# StearnsMT.net
KiCad netlist of a schematic drawn in EAGLE
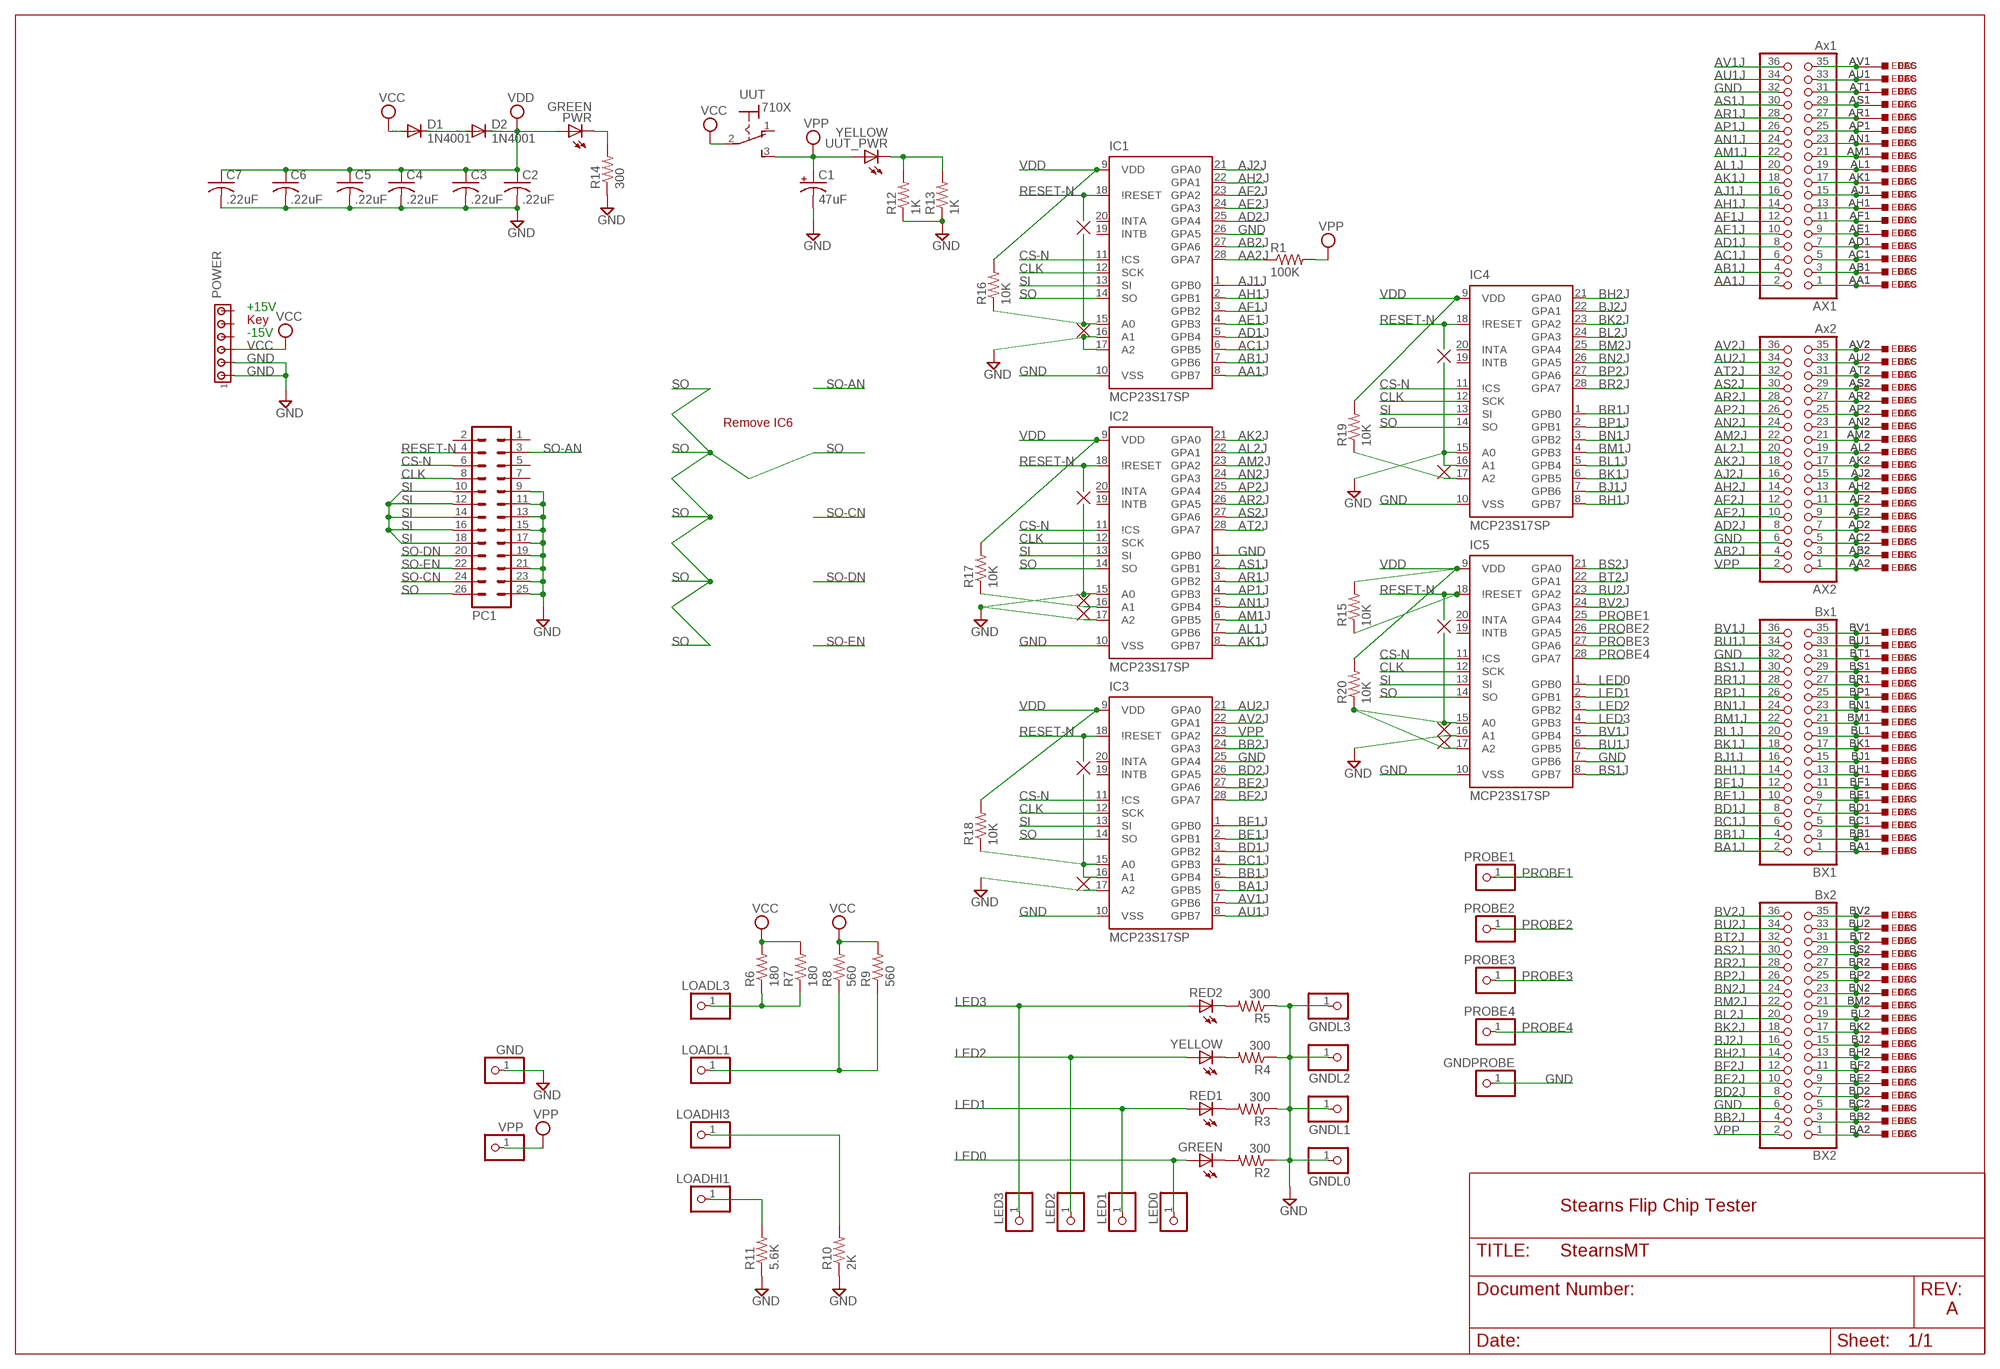
[diagram p0: schematic, sheet 1]

(export (version "E")
  (design (tool "Eeschema 10.0.6"))
  (components
    (comp (ref "AX1")
      (value "Ax1")
      (footprint "eagle-import:2X18")
      (libsource (lib "eagle-import") (part "PINHD-2X18"))
    )
    (comp (ref "AX2")
      (value "Ax2")
      (footprint "eagle-import:2X18")
      (libsource (lib "eagle-import") (part "PINHD-2X18"))
    )
    (comp (ref "BX1")
      (value "Bx1")
      (footprint "eagle-import:2X18")
      (libsource (lib "eagle-import") (part "PINHD-2X18"))
    )
    (comp (ref "BX2")
      (value "Bx2")
      (footprint "eagle-import:2X18")
      (libsource (lib "eagle-import") (part "PINHD-2X18"))
    )
    (comp (ref "C1")
      (value "47uF")
      (footprint "eagle-import:E5-8,5")
      (libsource (lib "eagle-import") (part "CPOL-USE5-8.5"))
    )
    (comp (ref "C2")
      (value ".22uF")
      (footprint "eagle-import:C050-025X075")
      (libsource (lib "eagle-import") (part "C-US050-025X075"))
    )
    (comp (ref "C3")
      (value ".22uF")
      (footprint "eagle-import:C050-025X075")
      (libsource (lib "eagle-import") (part "C-US050-025X075"))
    )
    (comp (ref "C4")
      (value ".22uF")
      (footprint "eagle-import:C050-025X075")
      (libsource (lib "eagle-import") (part "C-US050-025X075"))
    )
    (comp (ref "C5")
      (value ".22uF")
      (footprint "eagle-import:C050-025X075")
      (libsource (lib "eagle-import") (part "C-US050-025X075"))
    )
    (comp (ref "C6")
      (value ".22uF")
      (footprint "eagle-import:C050-025X075")
      (libsource (lib "eagle-import") (part "C-US050-025X075"))
    )
    (comp (ref "C7")
      (value ".22uF")
      (footprint "eagle-import:C050-025X075")
      (libsource (lib "eagle-import") (part "C-US050-025X075"))
    )
    (comp (ref "D1")
      (value "1N4001")
      (footprint "eagle-import:DO41-10")
      (libsource (lib "eagle-import") (part "1N4004"))
    )
    (comp (ref "D2")
      (value "1N4001")
      (footprint "eagle-import:DO41-10")
      (libsource (lib "eagle-import") (part "1N4004"))
    )
    (comp (ref "DEC")
      (value "W971")
      (footprint "eagle-import:H807-2")
      (libsource (lib "eagle-import") (part "W971"))
    )
    (comp (ref "ECS")
      (value "W971ECS")
      (footprint "eagle-import:ECS2418-2")
      (libsource (lib "eagle-import") (part "W971ECS"))
    )
    (comp (ref "EDAC")
      (value "W971EDAC")
      (footprint "eagle-import:EDAC346-36-2")
      (libsource (lib "eagle-import") (part "W971EDAC"))
    )
    (comp (ref "GND")
      (value "PINHD-1X1")
      (footprint "eagle-import:1X01")
      (libsource (lib "eagle-import") (part "PINHD-1X1"))
    )
    (comp (ref "GNDL0")
      (value "PINHD-1X1")
      (footprint "eagle-import:1X01")
      (libsource (lib "eagle-import") (part "PINHD-1X1"))
    )
    (comp (ref "GNDL1")
      (value "PINHD-1X1")
      (footprint "eagle-import:1X01")
      (libsource (lib "eagle-import") (part "PINHD-1X1"))
    )
    (comp (ref "GNDL2")
      (value "PINHD-1X1")
      (footprint "eagle-import:1X01")
      (libsource (lib "eagle-import") (part "PINHD-1X1"))
    )
    (comp (ref "GNDL3")
      (value "PINHD-1X1")
      (footprint "eagle-import:1X01")
      (libsource (lib "eagle-import") (part "PINHD-1X1"))
    )
    (comp (ref "GNDPROBE")
      (value "PINHD-1X1")
      (footprint "eagle-import:1X01")
      (libsource (lib "eagle-import") (part "PINHD-1X1"))
    )
    (comp (ref "GREEN")
      (value "LED5MM")
      (footprint "eagle-import:LED5MM")
      (libsource (lib "eagle-import") (part "LED5MM"))
    )
    (comp (ref "IC1")
      (value "MCP23S17SP")
      (footprint "eagle-import:DIL28-3")
      (libsource (lib "eagle-import") (part "MCP23S17SP"))
    )
    (comp (ref "IC2")
      (value "MCP23S17SP")
      (footprint "eagle-import:DIL28-3")
      (libsource (lib "eagle-import") (part "MCP23S17SP"))
    )
    (comp (ref "IC3")
      (value "MCP23S17SP")
      (footprint "eagle-import:DIL28-3")
      (libsource (lib "eagle-import") (part "MCP23S17SP"))
    )
    (comp (ref "IC4")
      (value "MCP23S17SP")
      (footprint "eagle-import:DIL28-3")
      (libsource (lib "eagle-import") (part "MCP23S17SP"))
    )
    (comp (ref "IC5")
      (value "MCP23S17SP")
      (footprint "eagle-import:DIL28-3")
      (libsource (lib "eagle-import") (part "MCP23S17SP"))
    )
    (comp (ref "LED0")
      (value "PINHD-1X1")
      (footprint "eagle-import:1X01")
      (libsource (lib "eagle-import") (part "PINHD-1X1"))
    )
    (comp (ref "LED1")
      (value "PINHD-1X1")
      (footprint "eagle-import:1X01")
      (libsource (lib "eagle-import") (part "PINHD-1X1"))
    )
    (comp (ref "LED2")
      (value "PINHD-1X1")
      (footprint "eagle-import:1X01")
      (libsource (lib "eagle-import") (part "PINHD-1X1"))
    )
    (comp (ref "LED3")
      (value "PINHD-1X1")
      (footprint "eagle-import:1X01")
      (libsource (lib "eagle-import") (part "PINHD-1X1"))
    )
    (comp (ref "LOADHI1")
      (value "PINHD-1X1")
      (footprint "eagle-import:1X01")
      (libsource (lib "eagle-import") (part "PINHD-1X1"))
    )
    (comp (ref "LOADHI3")
      (value "PINHD-1X1")
      (footprint "eagle-import:1X01")
      (libsource (lib "eagle-import") (part "PINHD-1X1"))
    )
    (comp (ref "LOADL1")
      (value "PINHD-1X1")
      (footprint "eagle-import:1X01")
      (libsource (lib "eagle-import") (part "PINHD-1X1"))
    )
    (comp (ref "LOADL3")
      (value "PINHD-1X1")
      (footprint "eagle-import:1X01")
      (libsource (lib "eagle-import") (part "PINHD-1X1"))
    )
    (comp (ref "PC1")
      (value "MA13-2")
      (footprint "eagle-import:MA13-2")
      (libsource (lib "eagle-import") (part "MA13-2"))
    )
    (comp (ref "POWER")
      (value "MTA06-156")
      (footprint "eagle-import:1X6MTA")
      (libsource (lib "eagle-import") (part "MTA06-156"))
    )
    (comp (ref "PROBE1")
      (value "PINHD-1X1")
      (footprint "eagle-import:1X01")
      (libsource (lib "eagle-import") (part "PINHD-1X1"))
    )
    (comp (ref "PROBE2")
      (value "PINHD-1X1")
      (footprint "eagle-import:1X01")
      (libsource (lib "eagle-import") (part "PINHD-1X1"))
    )
    (comp (ref "PROBE3")
      (value "PINHD-1X1")
      (footprint "eagle-import:1X01")
      (libsource (lib "eagle-import") (part "PINHD-1X1"))
    )
    (comp (ref "PROBE4")
      (value "PINHD-1X1")
      (footprint "eagle-import:1X01")
      (libsource (lib "eagle-import") (part "PINHD-1X1"))
    )
    (comp (ref "PWR")
      (value "GREEN")
      (footprint "eagle-import:LED5MM")
      (libsource (lib "eagle-import") (part "LED5MM"))
    )
    (comp (ref "R1")
      (value "100K")
      (footprint "eagle-import:0207_10")
      (libsource (lib "eagle-import") (part "R-US_0207/10"))
    )
    (comp (ref "R2")
      (value "300")
      (footprint "eagle-import:0207_10")
      (libsource (lib "eagle-import") (part "R-US_0207/10"))
    )
    (comp (ref "R3")
      (value "300")
      (footprint "eagle-import:0207_10")
      (libsource (lib "eagle-import") (part "R-US_0207/10"))
    )
    (comp (ref "R4")
      (value "300")
      (footprint "eagle-import:0207_10")
      (libsource (lib "eagle-import") (part "R-US_0207/10"))
    )
    (comp (ref "R5")
      (value "300")
      (footprint "eagle-import:0207_10")
      (libsource (lib "eagle-import") (part "R-US_0207/10"))
    )
    (comp (ref "R6")
      (value "180")
      (footprint "eagle-import:0207_10")
      (libsource (lib "eagle-import") (part "R-US_0207/10"))
    )
    (comp (ref "R7")
      (value "180")
      (footprint "eagle-import:0207_10")
      (libsource (lib "eagle-import") (part "R-US_0207/10"))
    )
    (comp (ref "R8")
      (value "560")
      (footprint "eagle-import:0207_10")
      (libsource (lib "eagle-import") (part "R-US_0207/10"))
    )
    (comp (ref "R9")
      (value "560")
      (footprint "eagle-import:0207_10")
      (libsource (lib "eagle-import") (part "R-US_0207/10"))
    )
    (comp (ref "R10")
      (value "2K")
      (footprint "eagle-import:0207_10")
      (libsource (lib "eagle-import") (part "R-US_0207/10"))
    )
    (comp (ref "R11")
      (value "5.6K")
      (footprint "eagle-import:0207_10")
      (libsource (lib "eagle-import") (part "R-US_0207/10"))
    )
    (comp (ref "R12")
      (value "1K")
      (footprint "eagle-import:0207_10")
      (libsource (lib "eagle-import") (part "R-US_0207/10"))
    )
    (comp (ref "R13")
      (value "1K")
      (footprint "eagle-import:0207_10")
      (libsource (lib "eagle-import") (part "R-US_0207/10"))
    )
    (comp (ref "R14")
      (value "300")
      (footprint "eagle-import:0207_10")
      (libsource (lib "eagle-import") (part "R-US_0207/10"))
    )
    (comp (ref "R15")
      (value "10K")
      (footprint "eagle-import:0207_10")
      (libsource (lib "eagle-import") (part "R-US_0207/10"))
    )
    (comp (ref "R16")
      (value "10K")
      (footprint "eagle-import:0207_10")
      (libsource (lib "eagle-import") (part "R-US_0207/10"))
    )
    (comp (ref "R17")
      (value "10K")
      (footprint "eagle-import:0207_10")
      (libsource (lib "eagle-import") (part "R-US_0207/10"))
    )
    (comp (ref "R18")
      (value "10K")
      (footprint "eagle-import:0207_10")
      (libsource (lib "eagle-import") (part "R-US_0207/10"))
    )
    (comp (ref "R19")
      (value "10K")
      (footprint "eagle-import:0207_10")
      (libsource (lib "eagle-import") (part "R-US_0207/10"))
    )
    (comp (ref "R20")
      (value "10K")
      (footprint "eagle-import:0207_10")
      (libsource (lib "eagle-import") (part "R-US_0207/10"))
    )
    (comp (ref "RED1")
      (value "LED5MM")
      (footprint "eagle-import:LED5MM")
      (libsource (lib "eagle-import") (part "LED5MM"))
    )
    (comp (ref "RED2")
      (value "LED5MM")
      (footprint "eagle-import:LED5MM")
      (libsource (lib "eagle-import") (part "LED5MM"))
    )
    (comp (ref "UUT")
      (value "710X")
      (footprint "eagle-import:7109MD9V3")
      (libsource (lib "eagle-import") (part "710X"))
    )
    (comp (ref "UUT_PWR")
      (value "YELLOW")
      (footprint "eagle-import:LED5MM")
      (libsource (lib "eagle-import") (part "LED5MM"))
    )
    (comp (ref "VPP")
      (value "PINHD-1X1")
      (footprint "eagle-import:1X01")
      (libsource (lib "eagle-import") (part "PINHD-1X1"))
    )
    (comp (ref "YELLOW")
      (value "LED5MM")
      (footprint "eagle-import:LED5MM")
      (libsource (lib "eagle-import") (part "LED5MM"))
    )
  )
  (nets
    (net (code "1") (name "/AA1J") (class "Default")
      (node (ref "AX1") (pin "2") (pinfunction "2_2") (pintype "passive"))
      (node (ref "IC1") (pin "8") (pinfunction "GPB7_8") (pintype "bidirectional"))
    )
    (net (code "2") (name "/AA2J") (class "Default")
      (node (ref "IC1") (pin "28") (pinfunction "GPA7_28") (pintype "bidirectional"))
      (node (ref "R1") (pin "1") (pinfunction "1_1") (pintype "passive"))
    )
    (net (code "3") (name "/AB1J") (class "Default")
      (node (ref "AX1") (pin "4") (pinfunction "4_4") (pintype "passive"))
      (node (ref "IC1") (pin "7") (pinfunction "GPB6_7") (pintype "bidirectional"))
    )
    (net (code "4") (name "/AB2J") (class "Default")
      (node (ref "AX2") (pin "4") (pinfunction "4_4") (pintype "passive"))
      (node (ref "IC1") (pin "27") (pinfunction "GPA6_27") (pintype "bidirectional"))
    )
    (net (code "5") (name "/AC1J") (class "Default")
      (node (ref "AX1") (pin "6") (pinfunction "6_6") (pintype "passive"))
      (node (ref "IC1") (pin "6") (pinfunction "GPB5_6") (pintype "bidirectional"))
    )
    (net (code "6") (name "/AD1J") (class "Default")
      (node (ref "AX1") (pin "8") (pinfunction "8_8") (pintype "passive"))
      (node (ref "IC1") (pin "5") (pinfunction "GPB4_5") (pintype "bidirectional"))
    )
    (net (code "7") (name "/AD2J") (class "Default")
      (node (ref "AX2") (pin "8") (pinfunction "8_8") (pintype "passive"))
      (node (ref "IC1") (pin "25") (pinfunction "GPA4_25") (pintype "bidirectional"))
    )
    (net (code "8") (name "/AE1J") (class "Default")
      (node (ref "AX1") (pin "10") (pinfunction "10_10") (pintype "passive"))
      (node (ref "IC1") (pin "4") (pinfunction "GPB3_4") (pintype "bidirectional"))
    )
    (net (code "9") (name "/AE2J") (class "Default")
      (node (ref "AX2") (pin "10") (pinfunction "10_10") (pintype "passive"))
      (node (ref "IC1") (pin "24") (pinfunction "GPA3_24") (pintype "bidirectional"))
    )
    (net (code "10") (name "/AF1J") (class "Default")
      (node (ref "AX1") (pin "12") (pinfunction "12_12") (pintype "passive"))
      (node (ref "IC1") (pin "3") (pinfunction "GPB2_3") (pintype "bidirectional"))
    )
    (net (code "11") (name "/AF2J") (class "Default")
      (node (ref "AX2") (pin "12") (pinfunction "12_12") (pintype "passive"))
      (node (ref "IC1") (pin "23") (pinfunction "GPA2_23") (pintype "bidirectional"))
    )
    (net (code "12") (name "/AH1J") (class "Default")
      (node (ref "AX1") (pin "14") (pinfunction "14_14") (pintype "passive"))
      (node (ref "IC1") (pin "2") (pinfunction "GPB1_2") (pintype "bidirectional"))
    )
    (net (code "13") (name "/AH2J") (class "Default")
      (node (ref "AX2") (pin "14") (pinfunction "14_14") (pintype "passive"))
      (node (ref "IC1") (pin "22") (pinfunction "GPA1_22") (pintype "bidirectional"))
    )
    (net (code "14") (name "/AJ1J") (class "Default")
      (node (ref "AX1") (pin "16") (pinfunction "16_16") (pintype "passive"))
      (node (ref "IC1") (pin "1") (pinfunction "GPB0_1") (pintype "bidirectional"))
    )
    (net (code "15") (name "/AJ2J") (class "Default")
      (node (ref "AX2") (pin "16") (pinfunction "16_16") (pintype "passive"))
      (node (ref "IC1") (pin "21") (pinfunction "GPA0_21") (pintype "bidirectional"))
    )
    (net (code "16") (name "/AK1J") (class "Default")
      (node (ref "AX1") (pin "18") (pinfunction "18_18") (pintype "passive"))
      (node (ref "IC2") (pin "8") (pinfunction "GPB7_8") (pintype "bidirectional"))
    )
    (net (code "17") (name "/AK2J") (class "Default")
      (node (ref "AX2") (pin "18") (pinfunction "18_18") (pintype "passive"))
      (node (ref "IC2") (pin "21") (pinfunction "GPA0_21") (pintype "bidirectional"))
    )
    (net (code "18") (name "/AL1J") (class "Default")
      (node (ref "AX1") (pin "20") (pinfunction "20_20") (pintype "passive"))
      (node (ref "IC2") (pin "7") (pinfunction "GPB6_7") (pintype "bidirectional"))
    )
    (net (code "19") (name "/AL2J") (class "Default")
      (node (ref "AX2") (pin "20") (pinfunction "20_20") (pintype "passive"))
      (node (ref "IC2") (pin "22") (pinfunction "GPA1_22") (pintype "bidirectional"))
    )
    (net (code "20") (name "/AM1J") (class "Default")
      (node (ref "AX1") (pin "22") (pinfunction "22_22") (pintype "passive"))
      (node (ref "IC2") (pin "6") (pinfunction "GPB5_6") (pintype "bidirectional"))
    )
    (net (code "21") (name "/AM2J") (class "Default")
      (node (ref "AX2") (pin "22") (pinfunction "22_22") (pintype "passive"))
      (node (ref "IC2") (pin "23") (pinfunction "GPA2_23") (pintype "bidirectional"))
    )
    (net (code "22") (name "/AN1J") (class "Default")
      (node (ref "AX1") (pin "24") (pinfunction "24_24") (pintype "passive"))
      (node (ref "IC2") (pin "5") (pinfunction "GPB4_5") (pintype "bidirectional"))
    )
    (net (code "23") (name "/AN2J") (class "Default")
      (node (ref "AX2") (pin "24") (pinfunction "24_24") (pintype "passive"))
      (node (ref "IC2") (pin "24") (pinfunction "GPA3_24") (pintype "bidirectional"))
    )
    (net (code "24") (name "/AP1J") (class "Default")
      (node (ref "AX1") (pin "26") (pinfunction "26_26") (pintype "passive"))
      (node (ref "IC2") (pin "4") (pinfunction "GPB3_4") (pintype "bidirectional"))
    )
    (net (code "25") (name "/AP2J") (class "Default")
      (node (ref "AX2") (pin "26") (pinfunction "26_26") (pintype "passive"))
      (node (ref "IC2") (pin "25") (pinfunction "GPA4_25") (pintype "bidirectional"))
    )
    (net (code "26") (name "/AR1J") (class "Default")
      (node (ref "AX1") (pin "28") (pinfunction "28_28") (pintype "passive"))
      (node (ref "IC2") (pin "3") (pinfunction "GPB2_3") (pintype "bidirectional"))
    )
    (net (code "27") (name "/AR2J") (class "Default")
      (node (ref "AX2") (pin "28") (pinfunction "28_28") (pintype "passive"))
      (node (ref "IC2") (pin "26") (pinfunction "GPA5_26") (pintype "bidirectional"))
    )
    (net (code "28") (name "/AS1J") (class "Default")
      (node (ref "AX1") (pin "30") (pinfunction "30_30") (pintype "passive"))
      (node (ref "IC2") (pin "2") (pinfunction "GPB1_2") (pintype "bidirectional"))
    )
    (net (code "29") (name "/AS2J") (class "Default")
      (node (ref "AX2") (pin "30") (pinfunction "30_30") (pintype "passive"))
      (node (ref "IC2") (pin "27") (pinfunction "GPA6_27") (pintype "bidirectional"))
    )
    (net (code "30") (name "/AT2J") (class "Default")
      (node (ref "AX2") (pin "32") (pinfunction "32_32") (pintype "passive"))
      (node (ref "IC2") (pin "28") (pinfunction "GPA7_28") (pintype "bidirectional"))
    )
    (net (code "31") (name "/AU1J") (class "Default")
      (node (ref "AX1") (pin "34") (pinfunction "34_34") (pintype "passive"))
      (node (ref "IC3") (pin "8") (pinfunction "GPB7_8") (pintype "bidirectional"))
    )
    (net (code "32") (name "/AU2J") (class "Default")
      (node (ref "AX2") (pin "34") (pinfunction "34_34") (pintype "passive"))
      (node (ref "IC3") (pin "21") (pinfunction "GPA0_21") (pintype "bidirectional"))
    )
    (net (code "33") (name "/AV1J") (class "Default")
      (node (ref "AX1") (pin "36") (pinfunction "36_36") (pintype "passive"))
      (node (ref "IC3") (pin "7") (pinfunction "GPB6_7") (pintype "bidirectional"))
    )
    (net (code "34") (name "/AV2J") (class "Default")
      (node (ref "AX2") (pin "36") (pinfunction "36_36") (pintype "passive"))
      (node (ref "IC3") (pin "22") (pinfunction "GPA1_22") (pintype "bidirectional"))
    )
    (net (code "35") (name "/BA1J") (class "Default")
      (node (ref "BX1") (pin "2") (pinfunction "2_2") (pintype "passive"))
      (node (ref "IC3") (pin "6") (pinfunction "GPB5_6") (pintype "bidirectional"))
    )
    (net (code "36") (name "/BB1J") (class "Default")
      (node (ref "BX1") (pin "4") (pinfunction "4_4") (pintype "passive"))
      (node (ref "IC3") (pin "5") (pinfunction "GPB4_5") (pintype "bidirectional"))
    )
    (net (code "37") (name "/BB2J") (class "Default")
      (node (ref "BX2") (pin "4") (pinfunction "4_4") (pintype "passive"))
      (node (ref "IC3") (pin "24") (pinfunction "GPA3_24") (pintype "bidirectional"))
    )
    (net (code "38") (name "/BC1J") (class "Default")
      (node (ref "BX1") (pin "6") (pinfunction "6_6") (pintype "passive"))
      (node (ref "IC3") (pin "4") (pinfunction "GPB3_4") (pintype "bidirectional"))
    )
    (net (code "39") (name "/BD1J") (class "Default")
      (node (ref "BX1") (pin "8") (pinfunction "8_8") (pintype "passive"))
      (node (ref "IC3") (pin "3") (pinfunction "GPB2_3") (pintype "bidirectional"))
    )
    (net (code "40") (name "/BD2J") (class "Default")
      (node (ref "BX2") (pin "8") (pinfunction "8_8") (pintype "passive"))
      (node (ref "IC3") (pin "26") (pinfunction "GPA5_26") (pintype "bidirectional"))
    )
    (net (code "41") (name "/BE1J") (class "Default")
      (node (ref "BX1") (pin "10") (pinfunction "10_10") (pintype "passive"))
      (node (ref "IC3") (pin "2") (pinfunction "GPB1_2") (pintype "bidirectional"))
    )
    (net (code "42") (name "/BE2J") (class "Default")
      (node (ref "BX2") (pin "10") (pinfunction "10_10") (pintype "passive"))
      (node (ref "IC3") (pin "27") (pinfunction "GPA6_27") (pintype "bidirectional"))
    )
    (net (code "43") (name "/BF1J") (class "Default")
      (node (ref "BX1") (pin "12") (pinfunction "12_12") (pintype "passive"))
      (node (ref "IC3") (pin "1") (pinfunction "GPB0_1") (pintype "bidirectional"))
    )
    (net (code "44") (name "/BF2J") (class "Default")
      (node (ref "BX2") (pin "12") (pinfunction "12_12") (pintype "passive"))
      (node (ref "IC3") (pin "28") (pinfunction "GPA7_28") (pintype "bidirectional"))
    )
    (net (code "45") (name "/BH1J") (class "Default")
      (node (ref "BX1") (pin "14") (pinfunction "14_14") (pintype "passive"))
      (node (ref "IC4") (pin "8") (pinfunction "GPB7_8") (pintype "bidirectional"))
    )
    (net (code "46") (name "/BH2J") (class "Default")
      (node (ref "BX2") (pin "14") (pinfunction "14_14") (pintype "passive"))
      (node (ref "IC4") (pin "21") (pinfunction "GPA0_21") (pintype "bidirectional"))
    )
    (net (code "47") (name "/BJ1J") (class "Default")
      (node (ref "BX1") (pin "16") (pinfunction "16_16") (pintype "passive"))
      (node (ref "IC4") (pin "7") (pinfunction "GPB6_7") (pintype "bidirectional"))
    )
    (net (code "48") (name "/BJ2J") (class "Default")
      (node (ref "BX2") (pin "16") (pinfunction "16_16") (pintype "passive"))
      (node (ref "IC4") (pin "22") (pinfunction "GPA1_22") (pintype "bidirectional"))
    )
    (net (code "49") (name "/BK1J") (class "Default")
      (node (ref "BX1") (pin "18") (pinfunction "18_18") (pintype "passive"))
      (node (ref "IC4") (pin "6") (pinfunction "GPB5_6") (pintype "bidirectional"))
    )
    (net (code "50") (name "/BK2J") (class "Default")
      (node (ref "BX2") (pin "18") (pinfunction "18_18") (pintype "passive"))
      (node (ref "IC4") (pin "23") (pinfunction "GPA2_23") (pintype "bidirectional"))
    )
    (net (code "51") (name "/BL1J") (class "Default")
      (node (ref "BX1") (pin "20") (pinfunction "20_20") (pintype "passive"))
      (node (ref "IC4") (pin "5") (pinfunction "GPB4_5") (pintype "bidirectional"))
    )
    (net (code "52") (name "/BL2J") (class "Default")
      (node (ref "BX2") (pin "20") (pinfunction "20_20") (pintype "passive"))
      (node (ref "IC4") (pin "24") (pinfunction "GPA3_24") (pintype "bidirectional"))
    )
    (net (code "53") (name "/BM1J") (class "Default")
      (node (ref "BX1") (pin "22") (pinfunction "22_22") (pintype "passive"))
      (node (ref "IC4") (pin "4") (pinfunction "GPB3_4") (pintype "bidirectional"))
    )
    (net (code "54") (name "/BM2J") (class "Default")
      (node (ref "BX2") (pin "22") (pinfunction "22_22") (pintype "passive"))
      (node (ref "IC4") (pin "25") (pinfunction "GPA4_25") (pintype "bidirectional"))
    )
    (net (code "55") (name "/BN1J") (class "Default")
      (node (ref "BX1") (pin "24") (pinfunction "24_24") (pintype "passive"))
      (node (ref "IC4") (pin "3") (pinfunction "GPB2_3") (pintype "bidirectional"))
    )
    (net (code "56") (name "/BN2J") (class "Default")
      (node (ref "BX2") (pin "24") (pinfunction "24_24") (pintype "passive"))
      (node (ref "IC4") (pin "26") (pinfunction "GPA5_26") (pintype "bidirectional"))
    )
    (net (code "57") (name "/BP1J") (class "Default")
      (node (ref "BX1") (pin "26") (pinfunction "26_26") (pintype "passive"))
      (node (ref "IC4") (pin "2") (pinfunction "GPB1_2") (pintype "bidirectional"))
    )
    (net (code "58") (name "/BP2J") (class "Default")
      (node (ref "BX2") (pin "26") (pinfunction "26_26") (pintype "passive"))
      (node (ref "IC4") (pin "27") (pinfunction "GPA6_27") (pintype "bidirectional"))
    )
    (net (code "59") (name "/BR1J") (class "Default")
      (node (ref "BX1") (pin "28") (pinfunction "28_28") (pintype "passive"))
      (node (ref "IC4") (pin "1") (pinfunction "GPB0_1") (pintype "bidirectional"))
    )
    (net (code "60") (name "/BR2J") (class "Default")
      (node (ref "BX2") (pin "28") (pinfunction "28_28") (pintype "passive"))
      (node (ref "IC4") (pin "28") (pinfunction "GPA7_28") (pintype "bidirectional"))
    )
    (net (code "61") (name "/BS1J") (class "Default")
      (node (ref "BX1") (pin "30") (pinfunction "30_30") (pintype "passive"))
      (node (ref "IC5") (pin "8") (pinfunction "GPB7_8") (pintype "bidirectional"))
    )
    (net (code "62") (name "/BS2J") (class "Default")
      (node (ref "BX2") (pin "30") (pinfunction "30_30") (pintype "passive"))
      (node (ref "IC5") (pin "21") (pinfunction "GPA0_21") (pintype "bidirectional"))
    )
    (net (code "63") (name "/BT2J") (class "Default")
      (node (ref "BX2") (pin "32") (pinfunction "32_32") (pintype "passive"))
      (node (ref "IC5") (pin "22") (pinfunction "GPA1_22") (pintype "bidirectional"))
    )
    (net (code "64") (name "/BU1J") (class "Default")
      (node (ref "BX1") (pin "34") (pinfunction "34_34") (pintype "passive"))
      (node (ref "IC5") (pin "6") (pinfunction "GPB5_6") (pintype "bidirectional"))
    )
    (net (code "65") (name "/BU2J") (class "Default")
      (node (ref "BX2") (pin "34") (pinfunction "34_34") (pintype "passive"))
      (node (ref "IC5") (pin "23") (pinfunction "GPA2_23") (pintype "bidirectional"))
    )
    (net (code "66") (name "/BV1J") (class "Default")
      (node (ref "BX1") (pin "36") (pinfunction "36_36") (pintype "passive"))
      (node (ref "IC5") (pin "5") (pinfunction "GPB4_5") (pintype "bidirectional"))
    )
    (net (code "67") (name "/BV2J") (class "Default")
      (node (ref "BX2") (pin "36") (pinfunction "36_36") (pintype "passive"))
      (node (ref "IC5") (pin "24") (pinfunction "GPA3_24") (pintype "bidirectional"))
    )
    (net (code "68") (name "/CLK") (class "Default")
      (node (ref "IC1") (pin "12") (pinfunction "SCK_12") (pintype "input"))
      (node (ref "IC2") (pin "12") (pinfunction "SCK_12") (pintype "input"))
      (node (ref "IC3") (pin "12") (pinfunction "SCK_12") (pintype "input"))
      (node (ref "IC4") (pin "12") (pinfunction "SCK_12") (pintype "input"))
      (node (ref "IC5") (pin "12") (pinfunction "SCK_12") (pintype "input"))
      (node (ref "PC1") (pin "8") (pinfunction "8_8") (pintype "passive"))
    )
    (net (code "69") (name "/CS-N") (class "Default")
      (node (ref "IC1") (pin "11") (pinfunction "\\~{CS}_11") (pintype "input"))
      (node (ref "IC2") (pin "11") (pinfunction "\\~{CS}_11") (pintype "input"))
      (node (ref "IC3") (pin "11") (pinfunction "\\~{CS}_11") (pintype "input"))
      (node (ref "IC4") (pin "11") (pinfunction "\\~{CS}_11") (pintype "input"))
      (node (ref "IC5") (pin "11") (pinfunction "\\~{CS}_11") (pintype "input"))
      (node (ref "PC1") (pin "6") (pinfunction "6_6") (pintype "passive"))
    )
    (net (code "70") (name "/LED0") (class "Default")
      (node (ref "GREEN") (pin "A") (pinfunction "A_A") (pintype "passive"))
      (node (ref "IC5") (pin "1") (pinfunction "GPB0_1") (pintype "bidirectional"))
      (node (ref "LED0") (pin "1") (pinfunction "1_1") (pintype "passive"))
    )
    (net (code "71") (name "/LED1") (class "Default")
      (node (ref "IC5") (pin "2") (pinfunction "GPB1_2") (pintype "bidirectional"))
      (node (ref "LED1") (pin "1") (pinfunction "1_1") (pintype "passive"))
      (node (ref "RED1") (pin "A") (pinfunction "A_A") (pintype "passive"))
    )
    (net (code "72") (name "/LED2") (class "Default")
      (node (ref "IC5") (pin "3") (pinfunction "GPB2_3") (pintype "bidirectional"))
      (node (ref "LED2") (pin "1") (pinfunction "1_1") (pintype "passive"))
      (node (ref "YELLOW") (pin "A") (pinfunction "A_A") (pintype "passive"))
    )
    (net (code "73") (name "/LED3") (class "Default")
      (node (ref "IC5") (pin "4") (pinfunction "GPB3_4") (pintype "bidirectional"))
      (node (ref "LED3") (pin "1") (pinfunction "1_1") (pintype "passive"))
      (node (ref "RED2") (pin "A") (pinfunction "A_A") (pintype "passive"))
    )
    (net (code "74") (name "/PROBE1") (class "Default")
      (node (ref "IC5") (pin "25") (pinfunction "GPA4_25") (pintype "bidirectional"))
      (node (ref "PROBE1") (pin "1") (pinfunction "1_1") (pintype "passive"))
    )
    (net (code "75") (name "/PROBE2") (class "Default")
      (node (ref "IC5") (pin "26") (pinfunction "GPA5_26") (pintype "bidirectional"))
      (node (ref "PROBE2") (pin "1") (pinfunction "1_1") (pintype "passive"))
    )
    (net (code "76") (name "/PROBE3") (class "Default")
      (node (ref "IC5") (pin "27") (pinfunction "GPA6_27") (pintype "bidirectional"))
      (node (ref "PROBE3") (pin "1") (pinfunction "1_1") (pintype "passive"))
    )
    (net (code "77") (name "/PROBE4") (class "Default")
      (node (ref "IC5") (pin "28") (pinfunction "GPA7_28") (pintype "bidirectional"))
      (node (ref "PROBE4") (pin "1") (pinfunction "1_1") (pintype "passive"))
    )
    (net (code "78") (name "/RESET-N") (class "Default")
      (node (ref "IC1") (pin "18") (pinfunction "\\~{RESET}_18") (pintype "input"))
      (node (ref "IC2") (pin "18") (pinfunction "\\~{RESET}_18") (pintype "input"))
      (node (ref "IC3") (pin "18") (pinfunction "\\~{RESET}_18") (pintype "input"))
      (node (ref "IC4") (pin "18") (pinfunction "\\~{RESET}_18") (pintype "input"))
      (node (ref "IC5") (pin "18") (pinfunction "\\~{RESET}_18") (pintype "input"))
      (node (ref "PC1") (pin "4") (pinfunction "4_4") (pintype "passive"))
      (node (ref "R15") (pin "1") (pinfunction "1_1") (pintype "passive"))
    )
    (net (code "79") (name "/SI") (class "Default")
      (node (ref "IC1") (pin "13") (pinfunction "SI_13") (pintype "input"))
      (node (ref "IC2") (pin "13") (pinfunction "SI_13") (pintype "input"))
      (node (ref "IC3") (pin "13") (pinfunction "SI_13") (pintype "input"))
      (node (ref "IC4") (pin "13") (pinfunction "SI_13") (pintype "input"))
      (node (ref "IC5") (pin "13") (pinfunction "SI_13") (pintype "input"))
      (node (ref "PC1") (pin "10") (pinfunction "10_10") (pintype "passive"))
      (node (ref "PC1") (pin "12") (pinfunction "12_12") (pintype "passive"))
      (node (ref "PC1") (pin "14") (pinfunction "14_14") (pintype "passive"))
      (node (ref "PC1") (pin "16") (pinfunction "16_16") (pintype "passive"))
      (node (ref "PC1") (pin "18") (pinfunction "18_18") (pintype "passive"))
    )
    (net (code "80") (name "/SO") (class "Default")
      (node (ref "IC1") (pin "14") (pinfunction "SO_14") (pintype "output"))
      (node (ref "IC2") (pin "14") (pinfunction "SO_14") (pintype "output"))
      (node (ref "IC3") (pin "14") (pinfunction "SO_14") (pintype "output"))
      (node (ref "IC4") (pin "14") (pinfunction "SO_14") (pintype "output"))
      (node (ref "IC5") (pin "14") (pinfunction "SO_14") (pintype "output"))
      (node (ref "PC1") (pin "26") (pinfunction "26_26") (pintype "passive"))
    )
    (net (code "81") (name "/SO-AN") (class "Default")
      (node (ref "PC1") (pin "3") (pinfunction "3_3") (pintype "passive"))
    )
    (net (code "82") (name "/SO-CN") (class "Default")
      (node (ref "PC1") (pin "24") (pinfunction "24_24") (pintype "passive"))
    )
    (net (code "83") (name "/SO-DN") (class "Default")
      (node (ref "PC1") (pin "20") (pinfunction "20_20") (pintype "passive"))
    )
    (net (code "84") (name "/SO-EN") (class "Default")
      (node (ref "PC1") (pin "22") (pinfunction "22_22") (pintype "passive"))
    )
    (net (code "85") (name "GND") (class "Default")
      (node (ref "AX1") (pin "32") (pinfunction "32_32") (pintype "passive"))
      (node (ref "AX2") (pin "6") (pinfunction "6_6") (pintype "passive"))
      (node (ref "BX1") (pin "32") (pinfunction "32_32") (pintype "passive"))
      (node (ref "BX2") (pin "6") (pinfunction "6_6") (pintype "passive"))
      (node (ref "C1") (pin "-") (pinfunction "-_-") (pintype "passive"))
      (node (ref "C2") (pin "2") (pinfunction "2_2") (pintype "passive"))
      (node (ref "C3") (pin "2") (pinfunction "2_2") (pintype "passive"))
      (node (ref "C4") (pin "2") (pinfunction "2_2") (pintype "passive"))
      (node (ref "C5") (pin "2") (pinfunction "2_2") (pintype "passive"))
      (node (ref "C6") (pin "2") (pinfunction "2_2") (pintype "passive"))
      (node (ref "C7") (pin "2") (pinfunction "2_2") (pintype "passive"))
      (node (ref "GND") (pin "1") (pinfunction "1_1") (pintype "passive"))
      (node (ref "GNDL0") (pin "1") (pinfunction "1_1") (pintype "passive"))
      (node (ref "GNDL1") (pin "1") (pinfunction "1_1") (pintype "passive"))
      (node (ref "GNDL2") (pin "1") (pinfunction "1_1") (pintype "passive"))
      (node (ref "GNDL3") (pin "1") (pinfunction "1_1") (pintype "passive"))
      (node (ref "GNDPROBE") (pin "1") (pinfunction "1_1") (pintype "passive"))
      (node (ref "IC1") (pin "10") (pinfunction "VSS_10") (pintype "power_in"))
      (node (ref "IC1") (pin "16") (pinfunction "A1_16") (pintype "input"))
      (node (ref "IC1") (pin "17") (pinfunction "A2_17") (pintype "input"))
      (node (ref "IC1") (pin "26") (pinfunction "GPA5_26") (pintype "bidirectional"))
      (node (ref "IC2") (pin "1") (pinfunction "GPB0_1") (pintype "bidirectional"))
      (node (ref "IC2") (pin "10") (pinfunction "VSS_10") (pintype "power_in"))
      (node (ref "IC2") (pin "15") (pinfunction "A0_15") (pintype "input"))
      (node (ref "IC2") (pin "17") (pinfunction "A2_17") (pintype "input"))
      (node (ref "IC3") (pin "10") (pinfunction "VSS_10") (pintype "power_in"))
      (node (ref "IC3") (pin "17") (pinfunction "A2_17") (pintype "input"))
      (node (ref "IC3") (pin "25") (pinfunction "GPA4_25") (pintype "bidirectional"))
      (node (ref "IC4") (pin "10") (pinfunction "VSS_10") (pintype "power_in"))
      (node (ref "IC4") (pin "15") (pinfunction "A0_15") (pintype "input"))
      (node (ref "IC4") (pin "16") (pinfunction "A1_16") (pintype "input"))
      (node (ref "IC5") (pin "10") (pinfunction "VSS_10") (pintype "power_in"))
      (node (ref "IC5") (pin "16") (pinfunction "A1_16") (pintype "input"))
      (node (ref "IC5") (pin "7") (pinfunction "GPB6_7") (pintype "bidirectional"))
      (node (ref "PC1") (pin "11") (pinfunction "11_11") (pintype "passive"))
      (node (ref "PC1") (pin "13") (pinfunction "13_13") (pintype "passive"))
      (node (ref "PC1") (pin "15") (pinfunction "15_15") (pintype "passive"))
      (node (ref "PC1") (pin "17") (pinfunction "17_17") (pintype "passive"))
      (node (ref "PC1") (pin "19") (pinfunction "19_19") (pintype "passive"))
      (node (ref "PC1") (pin "21") (pinfunction "21_21") (pintype "passive"))
      (node (ref "PC1") (pin "23") (pinfunction "23_23") (pintype "passive"))
      (node (ref "PC1") (pin "25") (pinfunction "25_25") (pintype "passive"))
      (node (ref "PC1") (pin "9") (pinfunction "9_9") (pintype "passive"))
      (node (ref "POWER") (pin "1") (pinfunction "1_1") (pintype "passive"))
      (node (ref "POWER") (pin "2") (pinfunction "2_2") (pintype "passive"))
      (node (ref "R10") (pin "1") (pinfunction "1_1") (pintype "passive"))
      (node (ref "R11") (pin "1") (pinfunction "1_1") (pintype "passive"))
      (node (ref "R12") (pin "1") (pinfunction "1_1") (pintype "passive"))
      (node (ref "R13") (pin "1") (pinfunction "1_1") (pintype "passive"))
      (node (ref "R14") (pin "1") (pinfunction "1_1") (pintype "passive"))
      (node (ref "R2") (pin "1") (pinfunction "1_1") (pintype "passive"))
      (node (ref "R3") (pin "1") (pinfunction "1_1") (pintype "passive"))
      (node (ref "R4") (pin "1") (pinfunction "1_1") (pintype "passive"))
      (node (ref "R5") (pin "1") (pinfunction "1_1") (pintype "passive"))
    )
    (net (code "86") (name "Net-(D1-PadC)") (class "Default")
      (node (ref "D1") (pin "C") (pinfunction "C_C") (pintype "passive"))
      (node (ref "D2") (pin "A") (pinfunction "A_A") (pintype "passive"))
    )
    (net (code "87") (name "Net-(DECA-P$2)") (class "Default")
      (node (ref "AX1") (pin "1") (pinfunction "1_1") (pintype "passive"))
      (node (ref "DEC") (pin "AA1") (pinfunction "P$2_AA1") (pintype "bidirectional"))
      (node (ref "ECS") (pin "AA1") (pinfunction "P$2_AA1") (pintype "bidirectional"))
      (node (ref "EDAC") (pin "AA1") (pinfunction "P$2_AA1") (pintype "bidirectional"))
    )
    (net (code "88") (name "Net-(DECAA-P$2)") (class "Default")
      (node (ref "AX1") (pin "27") (pinfunction "27_27") (pintype "passive"))
      (node (ref "DEC") (pin "AR1") (pinfunction "P$2_AR1") (pintype "bidirectional"))
      (node (ref "ECS") (pin "AR1") (pinfunction "P$2_AR1") (pintype "bidirectional"))
      (node (ref "EDAC") (pin "AR1") (pinfunction "P$2_AR1") (pintype "bidirectional"))
    )
    (net (code "89") (name "Net-(DECAB-P$2)") (class "Default")
      (node (ref "AX2") (pin "27") (pinfunction "27_27") (pintype "passive"))
      (node (ref "DEC") (pin "AR2") (pinfunction "P$2_AR2") (pintype "bidirectional"))
      (node (ref "ECS") (pin "AR2") (pinfunction "P$2_AR2") (pintype "bidirectional"))
      (node (ref "EDAC") (pin "AR2") (pinfunction "P$2_AR2") (pintype "bidirectional"))
    )
    (net (code "90") (name "Net-(DECAC-P$2)") (class "Default")
      (node (ref "AX1") (pin "29") (pinfunction "29_29") (pintype "passive"))
      (node (ref "DEC") (pin "AS1") (pinfunction "P$2_AS1") (pintype "bidirectional"))
      (node (ref "ECS") (pin "AS1") (pinfunction "P$2_AS1") (pintype "bidirectional"))
      (node (ref "EDAC") (pin "AS1") (pinfunction "P$2_AS1") (pintype "bidirectional"))
    )
    (net (code "91") (name "Net-(DECAD-P$2)") (class "Default")
      (node (ref "AX2") (pin "29") (pinfunction "29_29") (pintype "passive"))
      (node (ref "DEC") (pin "AS2") (pinfunction "P$2_AS2") (pintype "bidirectional"))
      (node (ref "ECS") (pin "AS2") (pinfunction "P$2_AS2") (pintype "bidirectional"))
      (node (ref "EDAC") (pin "AS2") (pinfunction "P$2_AS2") (pintype "bidirectional"))
    )
    (net (code "92") (name "Net-(DECAE-P$2)") (class "Default")
      (node (ref "AX1") (pin "31") (pinfunction "31_31") (pintype "passive"))
      (node (ref "DEC") (pin "AT1") (pinfunction "P$2_AT1") (pintype "bidirectional"))
      (node (ref "ECS") (pin "AT1") (pinfunction "P$2_AT1") (pintype "bidirectional"))
      (node (ref "EDAC") (pin "AT1") (pinfunction "P$2_AT1") (pintype "bidirectional"))
    )
    (net (code "93") (name "Net-(DECAF-P$2)") (class "Default")
      (node (ref "AX2") (pin "31") (pinfunction "31_31") (pintype "passive"))
      (node (ref "DEC") (pin "AT2") (pinfunction "P$2_AT2") (pintype "bidirectional"))
      (node (ref "ECS") (pin "AT2") (pinfunction "P$2_AT2") (pintype "bidirectional"))
      (node (ref "EDAC") (pin "AT2") (pinfunction "P$2_AT2") (pintype "bidirectional"))
    )
    (net (code "94") (name "Net-(DECAG-P$2)") (class "Default")
      (node (ref "AX1") (pin "33") (pinfunction "33_33") (pintype "passive"))
      (node (ref "DEC") (pin "AU1") (pinfunction "P$2_AU1") (pintype "bidirectional"))
      (node (ref "ECS") (pin "AU1") (pinfunction "P$2_AU1") (pintype "bidirectional"))
      (node (ref "EDAC") (pin "AU1") (pinfunction "P$2_AU1") (pintype "bidirectional"))
    )
    (net (code "95") (name "Net-(DECAH-P$2)") (class "Default")
      (node (ref "AX2") (pin "33") (pinfunction "33_33") (pintype "passive"))
      (node (ref "DEC") (pin "AU2") (pinfunction "P$2_AU2") (pintype "bidirectional"))
      (node (ref "ECS") (pin "AU2") (pinfunction "P$2_AU2") (pintype "bidirectional"))
      (node (ref "EDAC") (pin "AU2") (pinfunction "P$2_AU2") (pintype "bidirectional"))
    )
    (net (code "96") (name "Net-(DECAI-P$2)") (class "Default")
      (node (ref "AX1") (pin "35") (pinfunction "35_35") (pintype "passive"))
      (node (ref "DEC") (pin "AV1") (pinfunction "P$2_AV1") (pintype "bidirectional"))
      (node (ref "ECS") (pin "AV1") (pinfunction "P$2_AV1") (pintype "bidirectional"))
      (node (ref "EDAC") (pin "AV1") (pinfunction "P$2_AV1") (pintype "bidirectional"))
    )
    (net (code "97") (name "Net-(DECAJ-P$2)") (class "Default")
      (node (ref "AX2") (pin "35") (pinfunction "35_35") (pintype "passive"))
      (node (ref "DEC") (pin "AV2") (pinfunction "P$2_AV2") (pintype "bidirectional"))
      (node (ref "ECS") (pin "AV2") (pinfunction "P$2_AV2") (pintype "bidirectional"))
      (node (ref "EDAC") (pin "AV2") (pinfunction "P$2_AV2") (pintype "bidirectional"))
    )
    (net (code "98") (name "Net-(DECAK-P$2)") (class "Default")
      (node (ref "BX1") (pin "1") (pinfunction "1_1") (pintype "passive"))
      (node (ref "DEC") (pin "BA1") (pinfunction "P$2_BA1") (pintype "bidirectional"))
      (node (ref "ECS") (pin "BA1") (pinfunction "P$2_BA1") (pintype "bidirectional"))
      (node (ref "EDAC") (pin "BA1") (pinfunction "P$2_BA1") (pintype "bidirectional"))
    )
    (net (code "99") (name "Net-(DECAL-P$2)") (class "Default")
      (node (ref "BX2") (pin "1") (pinfunction "1_1") (pintype "passive"))
      (node (ref "DEC") (pin "BA2") (pinfunction "P$2_BA2") (pintype "bidirectional"))
      (node (ref "ECS") (pin "BA2") (pinfunction "P$2_BA2") (pintype "bidirectional"))
      (node (ref "EDAC") (pin "BA2") (pinfunction "P$2_BA2") (pintype "bidirectional"))
    )
    (net (code "100") (name "Net-(DECAM-P$2)") (class "Default")
      (node (ref "BX1") (pin "3") (pinfunction "3_3") (pintype "passive"))
      (node (ref "DEC") (pin "BB1") (pinfunction "P$2_BB1") (pintype "bidirectional"))
      (node (ref "ECS") (pin "BB1") (pinfunction "P$2_BB1") (pintype "bidirectional"))
      (node (ref "EDAC") (pin "BB1") (pinfunction "P$2_BB1") (pintype "bidirectional"))
    )
    (net (code "101") (name "Net-(DECAN-P$2)") (class "Default")
      (node (ref "BX2") (pin "3") (pinfunction "3_3") (pintype "passive"))
      (node (ref "DEC") (pin "BB2") (pinfunction "P$2_BB2") (pintype "bidirectional"))
      (node (ref "ECS") (pin "BB2") (pinfunction "P$2_BB2") (pintype "bidirectional"))
      (node (ref "EDAC") (pin "BB2") (pinfunction "P$2_BB2") (pintype "bidirectional"))
    )
    (net (code "102") (name "Net-(DECAO-P$2)") (class "Default")
      (node (ref "BX1") (pin "5") (pinfunction "5_5") (pintype "passive"))
      (node (ref "DEC") (pin "BC1") (pinfunction "P$2_BC1") (pintype "bidirectional"))
      (node (ref "ECS") (pin "BC1") (pinfunction "P$2_BC1") (pintype "bidirectional"))
      (node (ref "EDAC") (pin "BC1") (pinfunction "P$2_BC1") (pintype "bidirectional"))
    )
    (net (code "103") (name "Net-(DECAP-P$2)") (class "Default")
      (node (ref "BX2") (pin "5") (pinfunction "5_5") (pintype "passive"))
      (node (ref "DEC") (pin "BC2") (pinfunction "P$2_BC2") (pintype "bidirectional"))
      (node (ref "ECS") (pin "BC2") (pinfunction "P$2_BC2") (pintype "bidirectional"))
      (node (ref "EDAC") (pin "BC2") (pinfunction "P$2_BC2") (pintype "bidirectional"))
    )
    (net (code "104") (name "Net-(DECAQ-P$2)") (class "Default")
      (node (ref "BX1") (pin "7") (pinfunction "7_7") (pintype "passive"))
      (node (ref "DEC") (pin "BD1") (pinfunction "P$2_BD1") (pintype "bidirectional"))
      (node (ref "ECS") (pin "BD1") (pinfunction "P$2_BD1") (pintype "bidirectional"))
      (node (ref "EDAC") (pin "BD1") (pinfunction "P$2_BD1") (pintype "bidirectional"))
    )
    (net (code "105") (name "Net-(DECAR-P$2)") (class "Default")
      (node (ref "BX2") (pin "7") (pinfunction "7_7") (pintype "passive"))
      (node (ref "DEC") (pin "BD2") (pinfunction "P$2_BD2") (pintype "bidirectional"))
      (node (ref "ECS") (pin "BD2") (pinfunction "P$2_BD2") (pintype "bidirectional"))
      (node (ref "EDAC") (pin "BD2") (pinfunction "P$2_BD2") (pintype "bidirectional"))
    )
    (net (code "106") (name "Net-(DECAS-P$2)") (class "Default")
      (node (ref "BX1") (pin "9") (pinfunction "9_9") (pintype "passive"))
      (node (ref "DEC") (pin "BE1") (pinfunction "P$2_BE1") (pintype "bidirectional"))
      (node (ref "ECS") (pin "BE1") (pinfunction "P$2_BE1") (pintype "bidirectional"))
      (node (ref "EDAC") (pin "BE1") (pinfunction "P$2_BE1") (pintype "bidirectional"))
    )
    (net (code "107") (name "Net-(DECAT-P$2)") (class "Default")
      (node (ref "BX2") (pin "9") (pinfunction "9_9") (pintype "passive"))
      (node (ref "DEC") (pin "BE2") (pinfunction "P$2_BE2") (pintype "bidirectional"))
      (node (ref "ECS") (pin "BE2") (pinfunction "P$2_BE2") (pintype "bidirectional"))
      (node (ref "EDAC") (pin "BE2") (pinfunction "P$2_BE2") (pintype "bidirectional"))
    )
    (net (code "108") (name "Net-(DECAU-P$2)") (class "Default")
      (node (ref "BX1") (pin "11") (pinfunction "11_11") (pintype "passive"))
      (node (ref "DEC") (pin "BF1") (pinfunction "P$2_BF1") (pintype "bidirectional"))
      (node (ref "ECS") (pin "BF1") (pinfunction "P$2_BF1") (pintype "bidirectional"))
      (node (ref "EDAC") (pin "BF1") (pinfunction "P$2_BF1") (pintype "bidirectional"))
    )
    (net (code "109") (name "Net-(DECAV-P$2)") (class "Default")
      (node (ref "BX2") (pin "11") (pinfunction "11_11") (pintype "passive"))
      (node (ref "DEC") (pin "BF2") (pinfunction "P$2_BF2") (pintype "bidirectional"))
      (node (ref "ECS") (pin "BF2") (pinfunction "P$2_BF2") (pintype "bidirectional"))
      (node (ref "EDAC") (pin "BF2") (pinfunction "P$2_BF2") (pintype "bidirectional"))
    )
    (net (code "110") (name "Net-(DECAW-P$2)") (class "Default")
      (node (ref "BX1") (pin "13") (pinfunction "13_13") (pintype "passive"))
      (node (ref "DEC") (pin "BH1") (pinfunction "P$2_BH1") (pintype "bidirectional"))
      (node (ref "ECS") (pin "BH1") (pinfunction "P$2_BH1") (pintype "bidirectional"))
      (node (ref "EDAC") (pin "BH1") (pinfunction "P$2_BH1") (pintype "bidirectional"))
    )
    (net (code "111") (name "Net-(DECAX-P$2)") (class "Default")
      (node (ref "BX2") (pin "13") (pinfunction "13_13") (pintype "passive"))
      (node (ref "DEC") (pin "BH2") (pinfunction "P$2_BH2") (pintype "bidirectional"))
      (node (ref "ECS") (pin "BH2") (pinfunction "P$2_BH2") (pintype "bidirectional"))
      (node (ref "EDAC") (pin "BH2") (pinfunction "P$2_BH2") (pintype "bidirectional"))
    )
    (net (code "112") (name "Net-(DECAY-P$2)") (class "Default")
      (node (ref "BX1") (pin "15") (pinfunction "15_15") (pintype "passive"))
      (node (ref "DEC") (pin "BJ1") (pinfunction "P$2_BJ1") (pintype "bidirectional"))
      (node (ref "ECS") (pin "BJ1") (pinfunction "P$2_BJ1") (pintype "bidirectional"))
      (node (ref "EDAC") (pin "BJ1") (pinfunction "P$2_BJ1") (pintype "bidirectional"))
    )
    (net (code "113") (name "Net-(DECAZ-P$2)") (class "Default")
      (node (ref "BX2") (pin "15") (pinfunction "15_15") (pintype "passive"))
      (node (ref "DEC") (pin "BJ2") (pinfunction "P$2_BJ2") (pintype "bidirectional"))
      (node (ref "ECS") (pin "BJ2") (pinfunction "P$2_BJ2") (pintype "bidirectional"))
      (node (ref "EDAC") (pin "BJ2") (pinfunction "P$2_BJ2") (pintype "bidirectional"))
    )
    (net (code "114") (name "Net-(DECB-P$2)") (class "Default")
      (node (ref "AX2") (pin "1") (pinfunction "1_1") (pintype "passive"))
      (node (ref "DEC") (pin "AA2") (pinfunction "P$2_AA2") (pintype "bidirectional"))
      (node (ref "ECS") (pin "AA2") (pinfunction "P$2_AA2") (pintype "bidirectional"))
      (node (ref "EDAC") (pin "AA2") (pinfunction "P$2_AA2") (pintype "bidirectional"))
    )
    (net (code "115") (name "Net-(DECBA-P$2)") (class "Default")
      (node (ref "BX1") (pin "17") (pinfunction "17_17") (pintype "passive"))
      (node (ref "DEC") (pin "BK1") (pinfunction "P$2_BK1") (pintype "bidirectional"))
      (node (ref "ECS") (pin "BK1") (pinfunction "P$2_BK1") (pintype "bidirectional"))
      (node (ref "EDAC") (pin "BK1") (pinfunction "P$2_BK1") (pintype "bidirectional"))
    )
    (net (code "116") (name "Net-(DECBB-P$2)") (class "Default")
      (node (ref "BX2") (pin "17") (pinfunction "17_17") (pintype "passive"))
      (node (ref "DEC") (pin "BK2") (pinfunction "P$2_BK2") (pintype "bidirectional"))
      (node (ref "ECS") (pin "BK2") (pinfunction "P$2_BK2") (pintype "bidirectional"))
      (node (ref "EDAC") (pin "BK2") (pinfunction "P$2_BK2") (pintype "bidirectional"))
    )
    (net (code "117") (name "Net-(DECBC-P$2)") (class "Default")
      (node (ref "BX1") (pin "19") (pinfunction "19_19") (pintype "passive"))
      (node (ref "DEC") (pin "BL1") (pinfunction "P$2_BL1") (pintype "bidirectional"))
      (node (ref "ECS") (pin "BL1") (pinfunction "P$2_BL1") (pintype "bidirectional"))
      (node (ref "EDAC") (pin "BL1") (pinfunction "P$2_BL1") (pintype "bidirectional"))
    )
    (net (code "118") (name "Net-(DECBD-P$2)") (class "Default")
      (node (ref "BX2") (pin "19") (pinfunction "19_19") (pintype "passive"))
      (node (ref "DEC") (pin "BL2") (pinfunction "P$2_BL2") (pintype "bidirectional"))
      (node (ref "ECS") (pin "BL2") (pinfunction "P$2_BL2") (pintype "bidirectional"))
      (node (ref "EDAC") (pin "BL2") (pinfunction "P$2_BL2") (pintype "bidirectional"))
    )
    (net (code "119") (name "Net-(DECBE-P$2)") (class "Default")
      (node (ref "BX1") (pin "21") (pinfunction "21_21") (pintype "passive"))
      (node (ref "DEC") (pin "BM1") (pinfunction "P$2_BM1") (pintype "bidirectional"))
      (node (ref "ECS") (pin "BM1") (pinfunction "P$2_BM1") (pintype "bidirectional"))
      (node (ref "EDAC") (pin "BM1") (pinfunction "P$2_BM1") (pintype "bidirectional"))
    )
    (net (code "120") (name "Net-(DECBF-P$2)") (class "Default")
      (node (ref "BX2") (pin "21") (pinfunction "21_21") (pintype "passive"))
      (node (ref "DEC") (pin "BM2") (pinfunction "P$2_BM2") (pintype "bidirectional"))
      (node (ref "ECS") (pin "BM2") (pinfunction "P$2_BM2") (pintype "bidirectional"))
      (node (ref "EDAC") (pin "BM2") (pinfunction "P$2_BM2") (pintype "bidirectional"))
    )
    (net (code "121") (name "Net-(DECBG-P$2)") (class "Default")
      (node (ref "BX1") (pin "23") (pinfunction "23_23") (pintype "passive"))
      (node (ref "DEC") (pin "BN1") (pinfunction "P$2_BN1") (pintype "bidirectional"))
      (node (ref "ECS") (pin "BN1") (pinfunction "P$2_BN1") (pintype "bidirectional"))
      (node (ref "EDAC") (pin "BN1") (pinfunction "P$2_BN1") (pintype "bidirectional"))
    )
    (net (code "122") (name "Net-(DECBH-P$2)") (class "Default")
      (node (ref "BX2") (pin "23") (pinfunction "23_23") (pintype "passive"))
      (node (ref "DEC") (pin "BN2") (pinfunction "P$2_BN2") (pintype "bidirectional"))
      (node (ref "ECS") (pin "BN2") (pinfunction "P$2_BN2") (pintype "bidirectional"))
      (node (ref "EDAC") (pin "BN2") (pinfunction "P$2_BN2") (pintype "bidirectional"))
    )
    (net (code "123") (name "Net-(DECBI-P$2)") (class "Default")
      (node (ref "BX1") (pin "25") (pinfunction "25_25") (pintype "passive"))
      (node (ref "DEC") (pin "BP1") (pinfunction "P$2_BP1") (pintype "bidirectional"))
      (node (ref "ECS") (pin "BP1") (pinfunction "P$2_BP1") (pintype "bidirectional"))
      (node (ref "EDAC") (pin "BP1") (pinfunction "P$2_BP1") (pintype "bidirectional"))
    )
    (net (code "124") (name "Net-(DECBJ-P$2)") (class "Default")
      (node (ref "BX2") (pin "25") (pinfunction "25_25") (pintype "passive"))
      (node (ref "DEC") (pin "BP2") (pinfunction "P$2_BP2") (pintype "bidirectional"))
      (node (ref "ECS") (pin "BP2") (pinfunction "P$2_BP2") (pintype "bidirectional"))
      (node (ref "EDAC") (pin "BP2") (pinfunction "P$2_BP2") (pintype "bidirectional"))
    )
    (net (code "125") (name "Net-(DECBK-P$2)") (class "Default")
      (node (ref "BX1") (pin "27") (pinfunction "27_27") (pintype "passive"))
      (node (ref "DEC") (pin "BR1") (pinfunction "P$2_BR1") (pintype "bidirectional"))
      (node (ref "ECS") (pin "BR1") (pinfunction "P$2_BR1") (pintype "bidirectional"))
      (node (ref "EDAC") (pin "BR1") (pinfunction "P$2_BR1") (pintype "bidirectional"))
    )
    (net (code "126") (name "Net-(DECBL-P$2)") (class "Default")
      (node (ref "BX2") (pin "27") (pinfunction "27_27") (pintype "passive"))
      (node (ref "DEC") (pin "BR2") (pinfunction "P$2_BR2") (pintype "bidirectional"))
      (node (ref "ECS") (pin "BR2") (pinfunction "P$2_BR2") (pintype "bidirectional"))
      (node (ref "EDAC") (pin "BR2") (pinfunction "P$2_BR2") (pintype "bidirectional"))
    )
    (net (code "127") (name "Net-(DECBM-P$2)") (class "Default")
      (node (ref "BX1") (pin "29") (pinfunction "29_29") (pintype "passive"))
      (node (ref "DEC") (pin "BS1") (pinfunction "P$2_BS1") (pintype "bidirectional"))
      (node (ref "ECS") (pin "BS1") (pinfunction "P$2_BS1") (pintype "bidirectional"))
      (node (ref "EDAC") (pin "BS1") (pinfunction "P$2_BS1") (pintype "bidirectional"))
    )
    (net (code "128") (name "Net-(DECBN-P$2)") (class "Default")
      (node (ref "BX2") (pin "29") (pinfunction "29_29") (pintype "passive"))
      (node (ref "DEC") (pin "BS2") (pinfunction "P$2_BS2") (pintype "bidirectional"))
      (node (ref "ECS") (pin "BS2") (pinfunction "P$2_BS2") (pintype "bidirectional"))
      (node (ref "EDAC") (pin "BS2") (pinfunction "P$2_BS2") (pintype "bidirectional"))
    )
    (net (code "129") (name "Net-(DECBO-P$2)") (class "Default")
      (node (ref "BX1") (pin "31") (pinfunction "31_31") (pintype "passive"))
      (node (ref "DEC") (pin "BT1") (pinfunction "P$2_BT1") (pintype "bidirectional"))
      (node (ref "ECS") (pin "BT1") (pinfunction "P$2_BT1") (pintype "bidirectional"))
      (node (ref "EDAC") (pin "BT1") (pinfunction "P$2_BT1") (pintype "bidirectional"))
    )
    (net (code "130") (name "Net-(DECBP-P$2)") (class "Default")
      (node (ref "BX2") (pin "31") (pinfunction "31_31") (pintype "passive"))
      (node (ref "DEC") (pin "BT2") (pinfunction "P$2_BT2") (pintype "bidirectional"))
      (node (ref "ECS") (pin "BT2") (pinfunction "P$2_BT2") (pintype "bidirectional"))
      (node (ref "EDAC") (pin "BT2") (pinfunction "P$2_BT2") (pintype "bidirectional"))
    )
    (net (code "131") (name "Net-(DECBQ-P$2)") (class "Default")
      (node (ref "BX1") (pin "33") (pinfunction "33_33") (pintype "passive"))
      (node (ref "DEC") (pin "BU1") (pinfunction "P$2_BU1") (pintype "bidirectional"))
      (node (ref "ECS") (pin "BU1") (pinfunction "P$2_BU1") (pintype "bidirectional"))
      (node (ref "EDAC") (pin "BU1") (pinfunction "P$2_BU1") (pintype "bidirectional"))
    )
    (net (code "132") (name "Net-(DECBR-P$2)") (class "Default")
      (node (ref "BX2") (pin "33") (pinfunction "33_33") (pintype "passive"))
      (node (ref "DEC") (pin "BU2") (pinfunction "P$2_BU2") (pintype "bidirectional"))
      (node (ref "ECS") (pin "BU2") (pinfunction "P$2_BU2") (pintype "bidirectional"))
      (node (ref "EDAC") (pin "BU2") (pinfunction "P$2_BU2") (pintype "bidirectional"))
    )
    (net (code "133") (name "Net-(DECBS-P$2)") (class "Default")
      (node (ref "BX1") (pin "35") (pinfunction "35_35") (pintype "passive"))
      (node (ref "DEC") (pin "BV1") (pinfunction "P$2_BV1") (pintype "bidirectional"))
      (node (ref "ECS") (pin "BV1") (pinfunction "P$2_BV1") (pintype "bidirectional"))
      (node (ref "EDAC") (pin "BV1") (pinfunction "P$2_BV1") (pintype "bidirectional"))
    )
    (net (code "134") (name "Net-(DECBT-P$2)") (class "Default")
      (node (ref "BX2") (pin "35") (pinfunction "35_35") (pintype "passive"))
      (node (ref "DEC") (pin "BV2") (pinfunction "P$2_BV2") (pintype "bidirectional"))
      (node (ref "ECS") (pin "BV2") (pinfunction "P$2_BV2") (pintype "bidirectional"))
      (node (ref "EDAC") (pin "BV2") (pinfunction "P$2_BV2") (pintype "bidirectional"))
    )
    (net (code "135") (name "Net-(DECC-P$2)") (class "Default")
      (node (ref "AX1") (pin "3") (pinfunction "3_3") (pintype "passive"))
      (node (ref "DEC") (pin "AB1") (pinfunction "P$2_AB1") (pintype "bidirectional"))
      (node (ref "ECS") (pin "AB1") (pinfunction "P$2_AB1") (pintype "bidirectional"))
      (node (ref "EDAC") (pin "AB1") (pinfunction "P$2_AB1") (pintype "bidirectional"))
    )
    (net (code "136") (name "Net-(DECD-P$2)") (class "Default")
      (node (ref "AX2") (pin "3") (pinfunction "3_3") (pintype "passive"))
      (node (ref "DEC") (pin "AB2") (pinfunction "P$2_AB2") (pintype "bidirectional"))
      (node (ref "ECS") (pin "AB2") (pinfunction "P$2_AB2") (pintype "bidirectional"))
      (node (ref "EDAC") (pin "AB2") (pinfunction "P$2_AB2") (pintype "bidirectional"))
    )
    (net (code "137") (name "Net-(DECE-P$2)") (class "Default")
      (node (ref "AX1") (pin "5") (pinfunction "5_5") (pintype "passive"))
      (node (ref "DEC") (pin "AC1") (pinfunction "P$2_AC1") (pintype "bidirectional"))
      (node (ref "ECS") (pin "AC1") (pinfunction "P$2_AC1") (pintype "bidirectional"))
      (node (ref "EDAC") (pin "AC1") (pinfunction "P$2_AC1") (pintype "bidirectional"))
    )
    (net (code "138") (name "Net-(DECF-P$2)") (class "Default")
      (node (ref "AX2") (pin "5") (pinfunction "5_5") (pintype "passive"))
      (node (ref "DEC") (pin "AC2") (pinfunction "P$2_AC2") (pintype "bidirectional"))
      (node (ref "ECS") (pin "AC2") (pinfunction "P$2_AC2") (pintype "bidirectional"))
      (node (ref "EDAC") (pin "AC2") (pinfunction "P$2_AC2") (pintype "bidirectional"))
    )
    (net (code "139") (name "Net-(DECG-P$2)") (class "Default")
      (node (ref "AX1") (pin "7") (pinfunction "7_7") (pintype "passive"))
      (node (ref "DEC") (pin "AD1") (pinfunction "P$2_AD1") (pintype "bidirectional"))
      (node (ref "ECS") (pin "AD1") (pinfunction "P$2_AD1") (pintype "bidirectional"))
      (node (ref "EDAC") (pin "AD1") (pinfunction "P$2_AD1") (pintype "bidirectional"))
    )
    (net (code "140") (name "Net-(DECH-P$2)") (class "Default")
      (node (ref "AX2") (pin "7") (pinfunction "7_7") (pintype "passive"))
      (node (ref "DEC") (pin "AD2") (pinfunction "P$2_AD2") (pintype "bidirectional"))
      (node (ref "ECS") (pin "AD2") (pinfunction "P$2_AD2") (pintype "bidirectional"))
      (node (ref "EDAC") (pin "AD2") (pinfunction "P$2_AD2") (pintype "bidirectional"))
    )
    (net (code "141") (name "Net-(DECI-P$2)") (class "Default")
      (node (ref "AX1") (pin "9") (pinfunction "9_9") (pintype "passive"))
      (node (ref "DEC") (pin "AE1") (pinfunction "P$2_AE1") (pintype "bidirectional"))
      (node (ref "ECS") (pin "AE1") (pinfunction "P$2_AE1") (pintype "bidirectional"))
      (node (ref "EDAC") (pin "AE1") (pinfunction "P$2_AE1") (pintype "bidirectional"))
    )
    (net (code "142") (name "Net-(DECJ-P$2)") (class "Default")
      (node (ref "AX2") (pin "9") (pinfunction "9_9") (pintype "passive"))
      (node (ref "DEC") (pin "AE2") (pinfunction "P$2_AE2") (pintype "bidirectional"))
      (node (ref "ECS") (pin "AE2") (pinfunction "P$2_AE2") (pintype "bidirectional"))
      (node (ref "EDAC") (pin "AE2") (pinfunction "P$2_AE2") (pintype "bidirectional"))
    )
    (net (code "143") (name "Net-(DECK-P$2)") (class "Default")
      (node (ref "AX1") (pin "11") (pinfunction "11_11") (pintype "passive"))
      (node (ref "DEC") (pin "AF1") (pinfunction "P$2_AF1") (pintype "bidirectional"))
      (node (ref "ECS") (pin "AF1") (pinfunction "P$2_AF1") (pintype "bidirectional"))
      (node (ref "EDAC") (pin "AF1") (pinfunction "P$2_AF1") (pintype "bidirectional"))
    )
    (net (code "144") (name "Net-(DECL-P$2)") (class "Default")
      (node (ref "AX2") (pin "11") (pinfunction "11_11") (pintype "passive"))
      (node (ref "DEC") (pin "AF2") (pinfunction "P$2_AF2") (pintype "bidirectional"))
      (node (ref "ECS") (pin "AF2") (pinfunction "P$2_AF2") (pintype "bidirectional"))
      (node (ref "EDAC") (pin "AF2") (pinfunction "P$2_AF2") (pintype "bidirectional"))
    )
    (net (code "145") (name "Net-(DECM-P$2)") (class "Default")
      (node (ref "AX1") (pin "13") (pinfunction "13_13") (pintype "passive"))
      (node (ref "DEC") (pin "AH1") (pinfunction "P$2_AH1") (pintype "bidirectional"))
      (node (ref "ECS") (pin "AH1") (pinfunction "P$2_AH1") (pintype "bidirectional"))
      (node (ref "EDAC") (pin "AH1") (pinfunction "P$2_AH1") (pintype "bidirectional"))
    )
    (net (code "146") (name "Net-(DECN-P$2)") (class "Default")
      (node (ref "AX2") (pin "13") (pinfunction "13_13") (pintype "passive"))
      (node (ref "DEC") (pin "AH2") (pinfunction "P$2_AH2") (pintype "bidirectional"))
      (node (ref "ECS") (pin "AH2") (pinfunction "P$2_AH2") (pintype "bidirectional"))
      (node (ref "EDAC") (pin "AH2") (pinfunction "P$2_AH2") (pintype "bidirectional"))
    )
    (net (code "147") (name "Net-(DECO-P$2)") (class "Default")
      (node (ref "AX1") (pin "15") (pinfunction "15_15") (pintype "passive"))
      (node (ref "DEC") (pin "AJ1") (pinfunction "P$2_AJ1") (pintype "bidirectional"))
      (node (ref "ECS") (pin "AJ1") (pinfunction "P$2_AJ1") (pintype "bidirectional"))
      (node (ref "EDAC") (pin "AJ1") (pinfunction "P$2_AJ1") (pintype "bidirectional"))
    )
    (net (code "148") (name "Net-(DECP-P$2)") (class "Default")
      (node (ref "AX2") (pin "15") (pinfunction "15_15") (pintype "passive"))
      (node (ref "DEC") (pin "AJ2") (pinfunction "P$2_AJ2") (pintype "bidirectional"))
      (node (ref "ECS") (pin "AJ2") (pinfunction "P$2_AJ2") (pintype "bidirectional"))
      (node (ref "EDAC") (pin "AJ2") (pinfunction "P$2_AJ2") (pintype "bidirectional"))
    )
    (net (code "149") (name "Net-(DECQ-P$2)") (class "Default")
      (node (ref "AX1") (pin "17") (pinfunction "17_17") (pintype "passive"))
      (node (ref "DEC") (pin "AK1") (pinfunction "P$2_AK1") (pintype "bidirectional"))
      (node (ref "ECS") (pin "AK1") (pinfunction "P$2_AK1") (pintype "bidirectional"))
      (node (ref "EDAC") (pin "AK1") (pinfunction "P$2_AK1") (pintype "bidirectional"))
    )
    (net (code "150") (name "Net-(DECR-P$2)") (class "Default")
      (node (ref "AX2") (pin "17") (pinfunction "17_17") (pintype "passive"))
      (node (ref "DEC") (pin "AK2") (pinfunction "P$2_AK2") (pintype "bidirectional"))
      (node (ref "ECS") (pin "AK2") (pinfunction "P$2_AK2") (pintype "bidirectional"))
      (node (ref "EDAC") (pin "AK2") (pinfunction "P$2_AK2") (pintype "bidirectional"))
    )
    (net (code "151") (name "Net-(DECS-P$2)") (class "Default")
      (node (ref "AX1") (pin "19") (pinfunction "19_19") (pintype "passive"))
      (node (ref "DEC") (pin "AL1") (pinfunction "P$2_AL1") (pintype "bidirectional"))
      (node (ref "ECS") (pin "AL1") (pinfunction "P$2_AL1") (pintype "bidirectional"))
      (node (ref "EDAC") (pin "AL1") (pinfunction "P$2_AL1") (pintype "bidirectional"))
    )
    (net (code "152") (name "Net-(DECT-P$2)") (class "Default")
      (node (ref "AX2") (pin "19") (pinfunction "19_19") (pintype "passive"))
      (node (ref "DEC") (pin "AL2") (pinfunction "P$2_AL2") (pintype "bidirectional"))
      (node (ref "ECS") (pin "AL2") (pinfunction "P$2_AL2") (pintype "bidirectional"))
      (node (ref "EDAC") (pin "AL2") (pinfunction "P$2_AL2") (pintype "bidirectional"))
    )
    (net (code "153") (name "Net-(DECU-P$2)") (class "Default")
      (node (ref "AX1") (pin "21") (pinfunction "21_21") (pintype "passive"))
      (node (ref "DEC") (pin "AM1") (pinfunction "P$2_AM1") (pintype "bidirectional"))
      (node (ref "ECS") (pin "AM1") (pinfunction "P$2_AM1") (pintype "bidirectional"))
      (node (ref "EDAC") (pin "AM1") (pinfunction "P$2_AM1") (pintype "bidirectional"))
    )
    (net (code "154") (name "Net-(DECV-P$2)") (class "Default")
      (node (ref "AX2") (pin "21") (pinfunction "21_21") (pintype "passive"))
      (node (ref "DEC") (pin "AM2") (pinfunction "P$2_AM2") (pintype "bidirectional"))
      (node (ref "ECS") (pin "AM2") (pinfunction "P$2_AM2") (pintype "bidirectional"))
      (node (ref "EDAC") (pin "AM2") (pinfunction "P$2_AM2") (pintype "bidirectional"))
    )
    (net (code "155") (name "Net-(DECW-P$2)") (class "Default")
      (node (ref "AX1") (pin "23") (pinfunction "23_23") (pintype "passive"))
      (node (ref "DEC") (pin "AN1") (pinfunction "P$2_AN1") (pintype "bidirectional"))
      (node (ref "ECS") (pin "AN1") (pinfunction "P$2_AN1") (pintype "bidirectional"))
      (node (ref "EDAC") (pin "AN1") (pinfunction "P$2_AN1") (pintype "bidirectional"))
    )
    (net (code "156") (name "Net-(DECX-P$2)") (class "Default")
      (node (ref "AX2") (pin "23") (pinfunction "23_23") (pintype "passive"))
      (node (ref "DEC") (pin "AN2") (pinfunction "P$2_AN2") (pintype "bidirectional"))
      (node (ref "ECS") (pin "AN2") (pinfunction "P$2_AN2") (pintype "bidirectional"))
      (node (ref "EDAC") (pin "AN2") (pinfunction "P$2_AN2") (pintype "bidirectional"))
    )
    (net (code "157") (name "Net-(DECY-P$2)") (class "Default")
      (node (ref "AX1") (pin "25") (pinfunction "25_25") (pintype "passive"))
      (node (ref "DEC") (pin "AP1") (pinfunction "P$2_AP1") (pintype "bidirectional"))
      (node (ref "ECS") (pin "AP1") (pinfunction "P$2_AP1") (pintype "bidirectional"))
      (node (ref "EDAC") (pin "AP1") (pinfunction "P$2_AP1") (pintype "bidirectional"))
    )
    (net (code "158") (name "Net-(DECZ-P$2)") (class "Default")
      (node (ref "AX2") (pin "25") (pinfunction "25_25") (pintype "passive"))
      (node (ref "DEC") (pin "AP2") (pinfunction "P$2_AP2") (pintype "bidirectional"))
      (node (ref "ECS") (pin "AP2") (pinfunction "P$2_AP2") (pintype "bidirectional"))
      (node (ref "EDAC") (pin "AP2") (pinfunction "P$2_AP2") (pintype "bidirectional"))
    )
    (net (code "159") (name "Net-(GREEN-C)") (class "Default")
      (node (ref "GREEN") (pin "K") (pinfunction "C_K") (pintype "passive"))
      (node (ref "R2") (pin "2") (pinfunction "2_2") (pintype "passive"))
    )
    (net (code "160") (name "Net-(IC1-A0)") (class "Default")
      (node (ref "IC1") (pin "15") (pinfunction "A0_15") (pintype "input"))
      (node (ref "R16") (pin "1") (pinfunction "1_1") (pintype "passive"))
    )
    (net (code "161") (name "Net-(IC2-A1)") (class "Default")
      (node (ref "IC2") (pin "16") (pinfunction "A1_16") (pintype "input"))
      (node (ref "R17") (pin "1") (pinfunction "1_1") (pintype "passive"))
    )
    (net (code "162") (name "Net-(IC3-A0)") (class "Default")
      (node (ref "IC3") (pin "15") (pinfunction "A0_15") (pintype "input"))
      (node (ref "IC3") (pin "16") (pinfunction "A1_16") (pintype "input"))
      (node (ref "R18") (pin "1") (pinfunction "1_1") (pintype "passive"))
    )
    (net (code "163") (name "Net-(IC4-A2)") (class "Default")
      (node (ref "IC4") (pin "17") (pinfunction "A2_17") (pintype "input"))
      (node (ref "R19") (pin "1") (pinfunction "1_1") (pintype "passive"))
    )
    (net (code "164") (name "Net-(IC5-A0)") (class "Default")
      (node (ref "IC5") (pin "15") (pinfunction "A0_15") (pintype "input"))
      (node (ref "IC5") (pin "17") (pinfunction "A2_17") (pintype "input"))
      (node (ref "R20") (pin "1") (pinfunction "1_1") (pintype "passive"))
    )
    (net (code "165") (name "Net-(LOADHI1-Pad1)") (class "Default")
      (node (ref "LOADHI1") (pin "1") (pinfunction "1_1") (pintype "passive"))
      (node (ref "R11") (pin "2") (pinfunction "2_2") (pintype "passive"))
    )
    (net (code "166") (name "Net-(LOADHI3-Pad1)") (class "Default")
      (node (ref "LOADHI3") (pin "1") (pinfunction "1_1") (pintype "passive"))
      (node (ref "R10") (pin "2") (pinfunction "2_2") (pintype "passive"))
    )
    (net (code "167") (name "Net-(LOADL1-Pad1)") (class "Default")
      (node (ref "LOADL1") (pin "1") (pinfunction "1_1") (pintype "passive"))
      (node (ref "R8") (pin "1") (pinfunction "1_1") (pintype "passive"))
      (node (ref "R9") (pin "1") (pinfunction "1_1") (pintype "passive"))
    )
    (net (code "168") (name "Net-(LOADL3-Pad1)") (class "Default")
      (node (ref "LOADL3") (pin "1") (pinfunction "1_1") (pintype "passive"))
      (node (ref "R6") (pin "1") (pinfunction "1_1") (pintype "passive"))
      (node (ref "R7") (pin "1") (pinfunction "1_1") (pintype "passive"))
    )
    (net (code "169") (name "Net-(PWR-C)") (class "Default")
      (node (ref "PWR") (pin "K") (pinfunction "C_K") (pintype "passive"))
      (node (ref "R14") (pin "2") (pinfunction "2_2") (pintype "passive"))
    )
    (net (code "170") (name "Net-(RED1-C)") (class "Default")
      (node (ref "R3") (pin "2") (pinfunction "2_2") (pintype "passive"))
      (node (ref "RED1") (pin "K") (pinfunction "C_K") (pintype "passive"))
    )
    (net (code "171") (name "Net-(RED2-C)") (class "Default")
      (node (ref "R5") (pin "2") (pinfunction "2_2") (pintype "passive"))
      (node (ref "RED2") (pin "K") (pinfunction "C_K") (pintype "passive"))
    )
    (net (code "172") (name "Net-(UUT_PWR-C)") (class "Default")
      (node (ref "R12") (pin "2") (pinfunction "2_2") (pintype "passive"))
      (node (ref "R13") (pin "2") (pinfunction "2_2") (pintype "passive"))
      (node (ref "UUT_PWR") (pin "K") (pinfunction "C_K") (pintype "passive"))
    )
    (net (code "173") (name "Net-(YELLOW-C)") (class "Default")
      (node (ref "R4") (pin "2") (pinfunction "2_2") (pintype "passive"))
      (node (ref "YELLOW") (pin "K") (pinfunction "C_K") (pintype "passive"))
    )
    (net (code "174") (name "VCC") (class "Default")
      (node (ref "D1") (pin "A") (pinfunction "A_A") (pintype "passive"))
      (node (ref "POWER") (pin "3") (pinfunction "3_3") (pintype "passive"))
      (node (ref "R6") (pin "2") (pinfunction "2_2") (pintype "passive"))
      (node (ref "R7") (pin "2") (pinfunction "2_2") (pintype "passive"))
      (node (ref "R8") (pin "2") (pinfunction "2_2") (pintype "passive"))
      (node (ref "R9") (pin "2") (pinfunction "2_2") (pintype "passive"))
      (node (ref "UUT") (pin "2") (pinfunction "P_2") (pintype "passive"))
    )
    (net (code "175") (name "VDD") (class "Default")
      (node (ref "C2") (pin "1") (pinfunction "1_1") (pintype "passive"))
      (node (ref "C3") (pin "1") (pinfunction "1_1") (pintype "passive"))
      (node (ref "C4") (pin "1") (pinfunction "1_1") (pintype "passive"))
      (node (ref "C5") (pin "1") (pinfunction "1_1") (pintype "passive"))
      (node (ref "C6") (pin "1") (pinfunction "1_1") (pintype "passive"))
      (node (ref "C7") (pin "1") (pinfunction "1_1") (pintype "passive"))
      (node (ref "D2") (pin "C") (pinfunction "C_C") (pintype "passive"))
      (node (ref "IC1") (pin "9") (pinfunction "VDD_9") (pintype "power_in"))
      (node (ref "IC2") (pin "9") (pinfunction "VDD_9") (pintype "power_in"))
      (node (ref "IC3") (pin "9") (pinfunction "VDD_9") (pintype "power_in"))
      (node (ref "IC4") (pin "9") (pinfunction "VDD_9") (pintype "power_in"))
      (node (ref "IC5") (pin "9") (pinfunction "VDD_9") (pintype "power_in"))
      (node (ref "PWR") (pin "A") (pinfunction "A_A") (pintype "passive"))
      (node (ref "R15") (pin "2") (pinfunction "2_2") (pintype "passive"))
      (node (ref "R16") (pin "2") (pinfunction "2_2") (pintype "passive"))
      (node (ref "R17") (pin "2") (pinfunction "2_2") (pintype "passive"))
      (node (ref "R18") (pin "2") (pinfunction "2_2") (pintype "passive"))
      (node (ref "R19") (pin "2") (pinfunction "2_2") (pintype "passive"))
      (node (ref "R20") (pin "2") (pinfunction "2_2") (pintype "passive"))
    )
    (net (code "176") (name "VPP") (class "Default")
      (node (ref "AX2") (pin "2") (pinfunction "2_2") (pintype "passive"))
      (node (ref "BX2") (pin "2") (pinfunction "2_2") (pintype "passive"))
      (node (ref "C1") (pin "+") (pinfunction "+_+") (pintype "passive"))
      (node (ref "IC3") (pin "23") (pinfunction "GPA2_23") (pintype "bidirectional"))
      (node (ref "R1") (pin "2") (pinfunction "2_2") (pintype "passive"))
      (node (ref "UUT") (pin "3") (pinfunction "S_3") (pintype "passive"))
      (node (ref "UUT_PWR") (pin "A") (pinfunction "A_A") (pintype "passive"))
      (node (ref "VPP") (pin "1") (pinfunction "1_1") (pintype "passive"))
    )
    (net (code "177") (name "unconnected-(IC1-INTA-Pad20)") (class "Default")
      (node (ref "IC1") (pin "20") (pinfunction "INTA_20") (pintype "output"))
    )
    (net (code "178") (name "unconnected-(IC1-INTB-Pad19)") (class "Default")
      (node (ref "IC1") (pin "19") (pinfunction "INTB_19") (pintype "output"))
    )
    (net (code "179") (name "unconnected-(IC2-INTA-Pad20)") (class "Default")
      (node (ref "IC2") (pin "20") (pinfunction "INTA_20") (pintype "output"))
    )
    (net (code "180") (name "unconnected-(IC2-INTB-Pad19)") (class "Default")
      (node (ref "IC2") (pin "19") (pinfunction "INTB_19") (pintype "output"))
    )
    (net (code "181") (name "unconnected-(IC3-INTA-Pad20)") (class "Default")
      (node (ref "IC3") (pin "20") (pinfunction "INTA_20") (pintype "output"))
    )
    (net (code "182") (name "unconnected-(IC3-INTB-Pad19)") (class "Default")
      (node (ref "IC3") (pin "19") (pinfunction "INTB_19") (pintype "output"))
    )
    (net (code "183") (name "unconnected-(IC4-INTA-Pad20)") (class "Default")
      (node (ref "IC4") (pin "20") (pinfunction "INTA_20") (pintype "output"))
    )
    (net (code "184") (name "unconnected-(IC4-INTB-Pad19)") (class "Default")
      (node (ref "IC4") (pin "19") (pinfunction "INTB_19") (pintype "output"))
    )
    (net (code "185") (name "unconnected-(IC5-INTA-Pad20)") (class "Default")
      (node (ref "IC5") (pin "20") (pinfunction "INTA_20") (pintype "output"))
    )
    (net (code "186") (name "unconnected-(IC5-INTB-Pad19)") (class "Default")
      (node (ref "IC5") (pin "19") (pinfunction "INTB_19") (pintype "output"))
    )
    (net (code "187") (name "unconnected-(PC1-Pad1)") (class "Default")
      (node (ref "PC1") (pin "1") (pinfunction "1_1") (pintype "passive"))
    )
    (net (code "188") (name "unconnected-(PC1-Pad2)") (class "Default")
      (node (ref "PC1") (pin "2") (pinfunction "2_2") (pintype "passive"))
    )
    (net (code "189") (name "unconnected-(PC1-Pad5)") (class "Default")
      (node (ref "PC1") (pin "5") (pinfunction "5_5") (pintype "passive"))
    )
    (net (code "190") (name "unconnected-(PC1-Pad7)") (class "Default")
      (node (ref "PC1") (pin "7") (pinfunction "7_7") (pintype "passive"))
    )
    (net (code "191") (name "unconnected-(POWER-Pad4)") (class "Default")
      (node (ref "POWER") (pin "4") (pinfunction "4_4") (pintype "passive"))
    )
    (net (code "192") (name "unconnected-(POWER-Pad5)") (class "Default")
      (node (ref "POWER") (pin "5") (pinfunction "5_5") (pintype "passive"))
    )
    (net (code "193") (name "unconnected-(POWER-Pad6)") (class "Default")
      (node (ref "POWER") (pin "6") (pinfunction "6_6") (pintype "passive"))
    )
    (net (code "194") (name "unconnected-(UUTA-O-Pad1)") (class "Default")
      (node (ref "UUT") (pin "1") (pinfunction "O_1") (pintype "passive"))
    )
  )
)
